# NFC__2021-03-03.net
KiCad netlist of a schematic drawn in Altium Designer
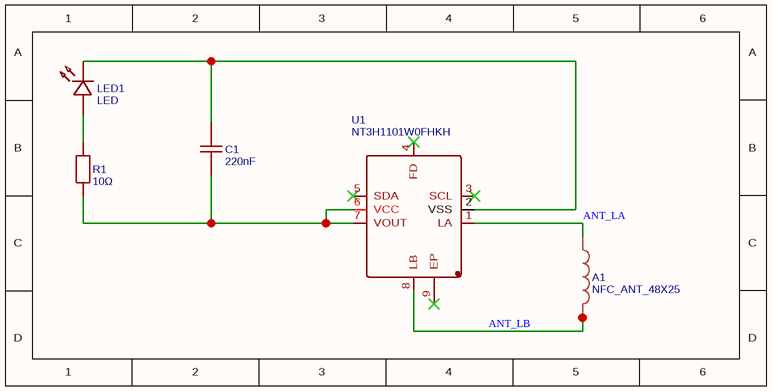
[diagram p0: NFC电子名片原理图_2021-03-03.schdoc]

(export (version "E")
  (design (tool "Eeschema 10.0.6"))
  (components
    (comp (ref "A1")
      (value "NFC_ANT_48X25")
      (fields (field (name "CONTRIBUTOR") "elio1997"))
      (libsource (lib "altium-import") (part "root_0_NFC_ANT_48X25_"))
    )
    (comp (ref "C1")
      (value "220nF")
      (fields
        (field (name "BOM_SUPPLIER PART") "C338153")
        (field (name "BOM_MANUFACTURER PART") "0603B224K160CT")
        (field (name "CONTRIBUTOR") "LCEDA_Lib")
      )
      (libsource (lib "altium-import") (part "root_1_220nF_"))
    )
    (comp (ref "LED1")
      (value "LED")
      (fields
        (field (name "BOM_MANUFACTURER PART") "NCD0603G2")
        (field (name "BOM_SUPPLIER PART") "C87326")
        (field (name "CONTRIBUTOR") "LCEDA_01")
      )
      (libsource (lib "altium-import") (part "root_1_LED_"))
    )
    (comp (ref "R1")
      (value "10Ω")
      (fields
        (field (name "BOM_SUPPLIER PART") "C22859")
        (field (name "BOM_MANUFACTURER PART") "0603WAF100JT5E")
        (field (name "CONTRIBUTOR") "LCEDA_Lib")
      )
      (libsource (lib "altium-import") (part "root_1_10Ω_"))
    )
    (comp (ref "U1")
      (value "NT3H1101W0FHKH")
      (fields (field (name "BOM_SUPPLIER PART") "C73156") (field (name "CONTRIBUTOR") "LCSC"))
      (libsource (lib "altium-import") (part "root_2_NT3H1101W0FHKH_"))
    )
  )
  (nets
    (net (code "1") (name "/ANT_LA") (class "Default")
      (node (ref "A1") (pin "A") (pinfunction "A_A") (pintype "passive"))
      (node (ref "U1") (pin "1") (pinfunction "LA_1") (pintype "passive"))
    )
    (net (code "2") (name "/ANT_LB") (class "Default")
      (node (ref "A1") (pin "B") (pinfunction "B_B") (pintype "passive"))
      (node (ref "A1") (pin "P$3") (pinfunction "B_P$3") (pintype "passive"))
      (node (ref "U1") (pin "8") (pinfunction "LB_8") (pintype "passive"))
    )
    (net (code "3") (name "Net-(LED1-Pad1)") (class "Default")
      (node (ref "LED1") (pin "1") (pinfunction "1_1") (pintype "passive"))
      (node (ref "R1") (pin "2") (pinfunction "2_2") (pintype "passive"))
    )
    (net (code "4") (name "Net-(U1-VCC)") (class "Default")
      (node (ref "C1") (pin "1") (pinfunction "1_1") (pintype "passive"))
      (node (ref "R1") (pin "1") (pinfunction "1_1") (pintype "passive"))
      (node (ref "U1") (pin "6") (pinfunction "VCC_6") (pintype "passive"))
      (node (ref "U1") (pin "7") (pinfunction "VOUT_7") (pintype "passive"))
    )
    (net (code "5") (name "Net-(U1-VSS)") (class "Default")
      (node (ref "C1") (pin "2") (pinfunction "2_2") (pintype "passive"))
      (node (ref "LED1") (pin "2") (pinfunction "2_2") (pintype "passive"))
      (node (ref "U1") (pin "2") (pinfunction "VSS_2") (pintype "passive"))
    )
    (net (code "6") (name "unconnected-(U1-EP-Pad9)") (class "Default")
      (node (ref "U1") (pin "9") (pinfunction "EP_9") (pintype "passive+no_connect"))
    )
    (net (code "7") (name "unconnected-(U1-FD-Pad4)") (class "Default")
      (node (ref "U1") (pin "4") (pinfunction "FD_4") (pintype "passive+no_connect"))
    )
    (net (code "8") (name "unconnected-(U1-SCL-Pad3)") (class "Default")
      (node (ref "U1") (pin "3") (pinfunction "SCL_3") (pintype "passive+no_connect"))
    )
    (net (code "9") (name "unconnected-(U1-SDA-Pad5)") (class "Default")
      (node (ref "U1") (pin "5") (pinfunction "SDA_5") (pintype "passive+no_connect"))
    )
  )
)
